# Controller.net
KiCad netlist of a schematic drawn in EasyEDA
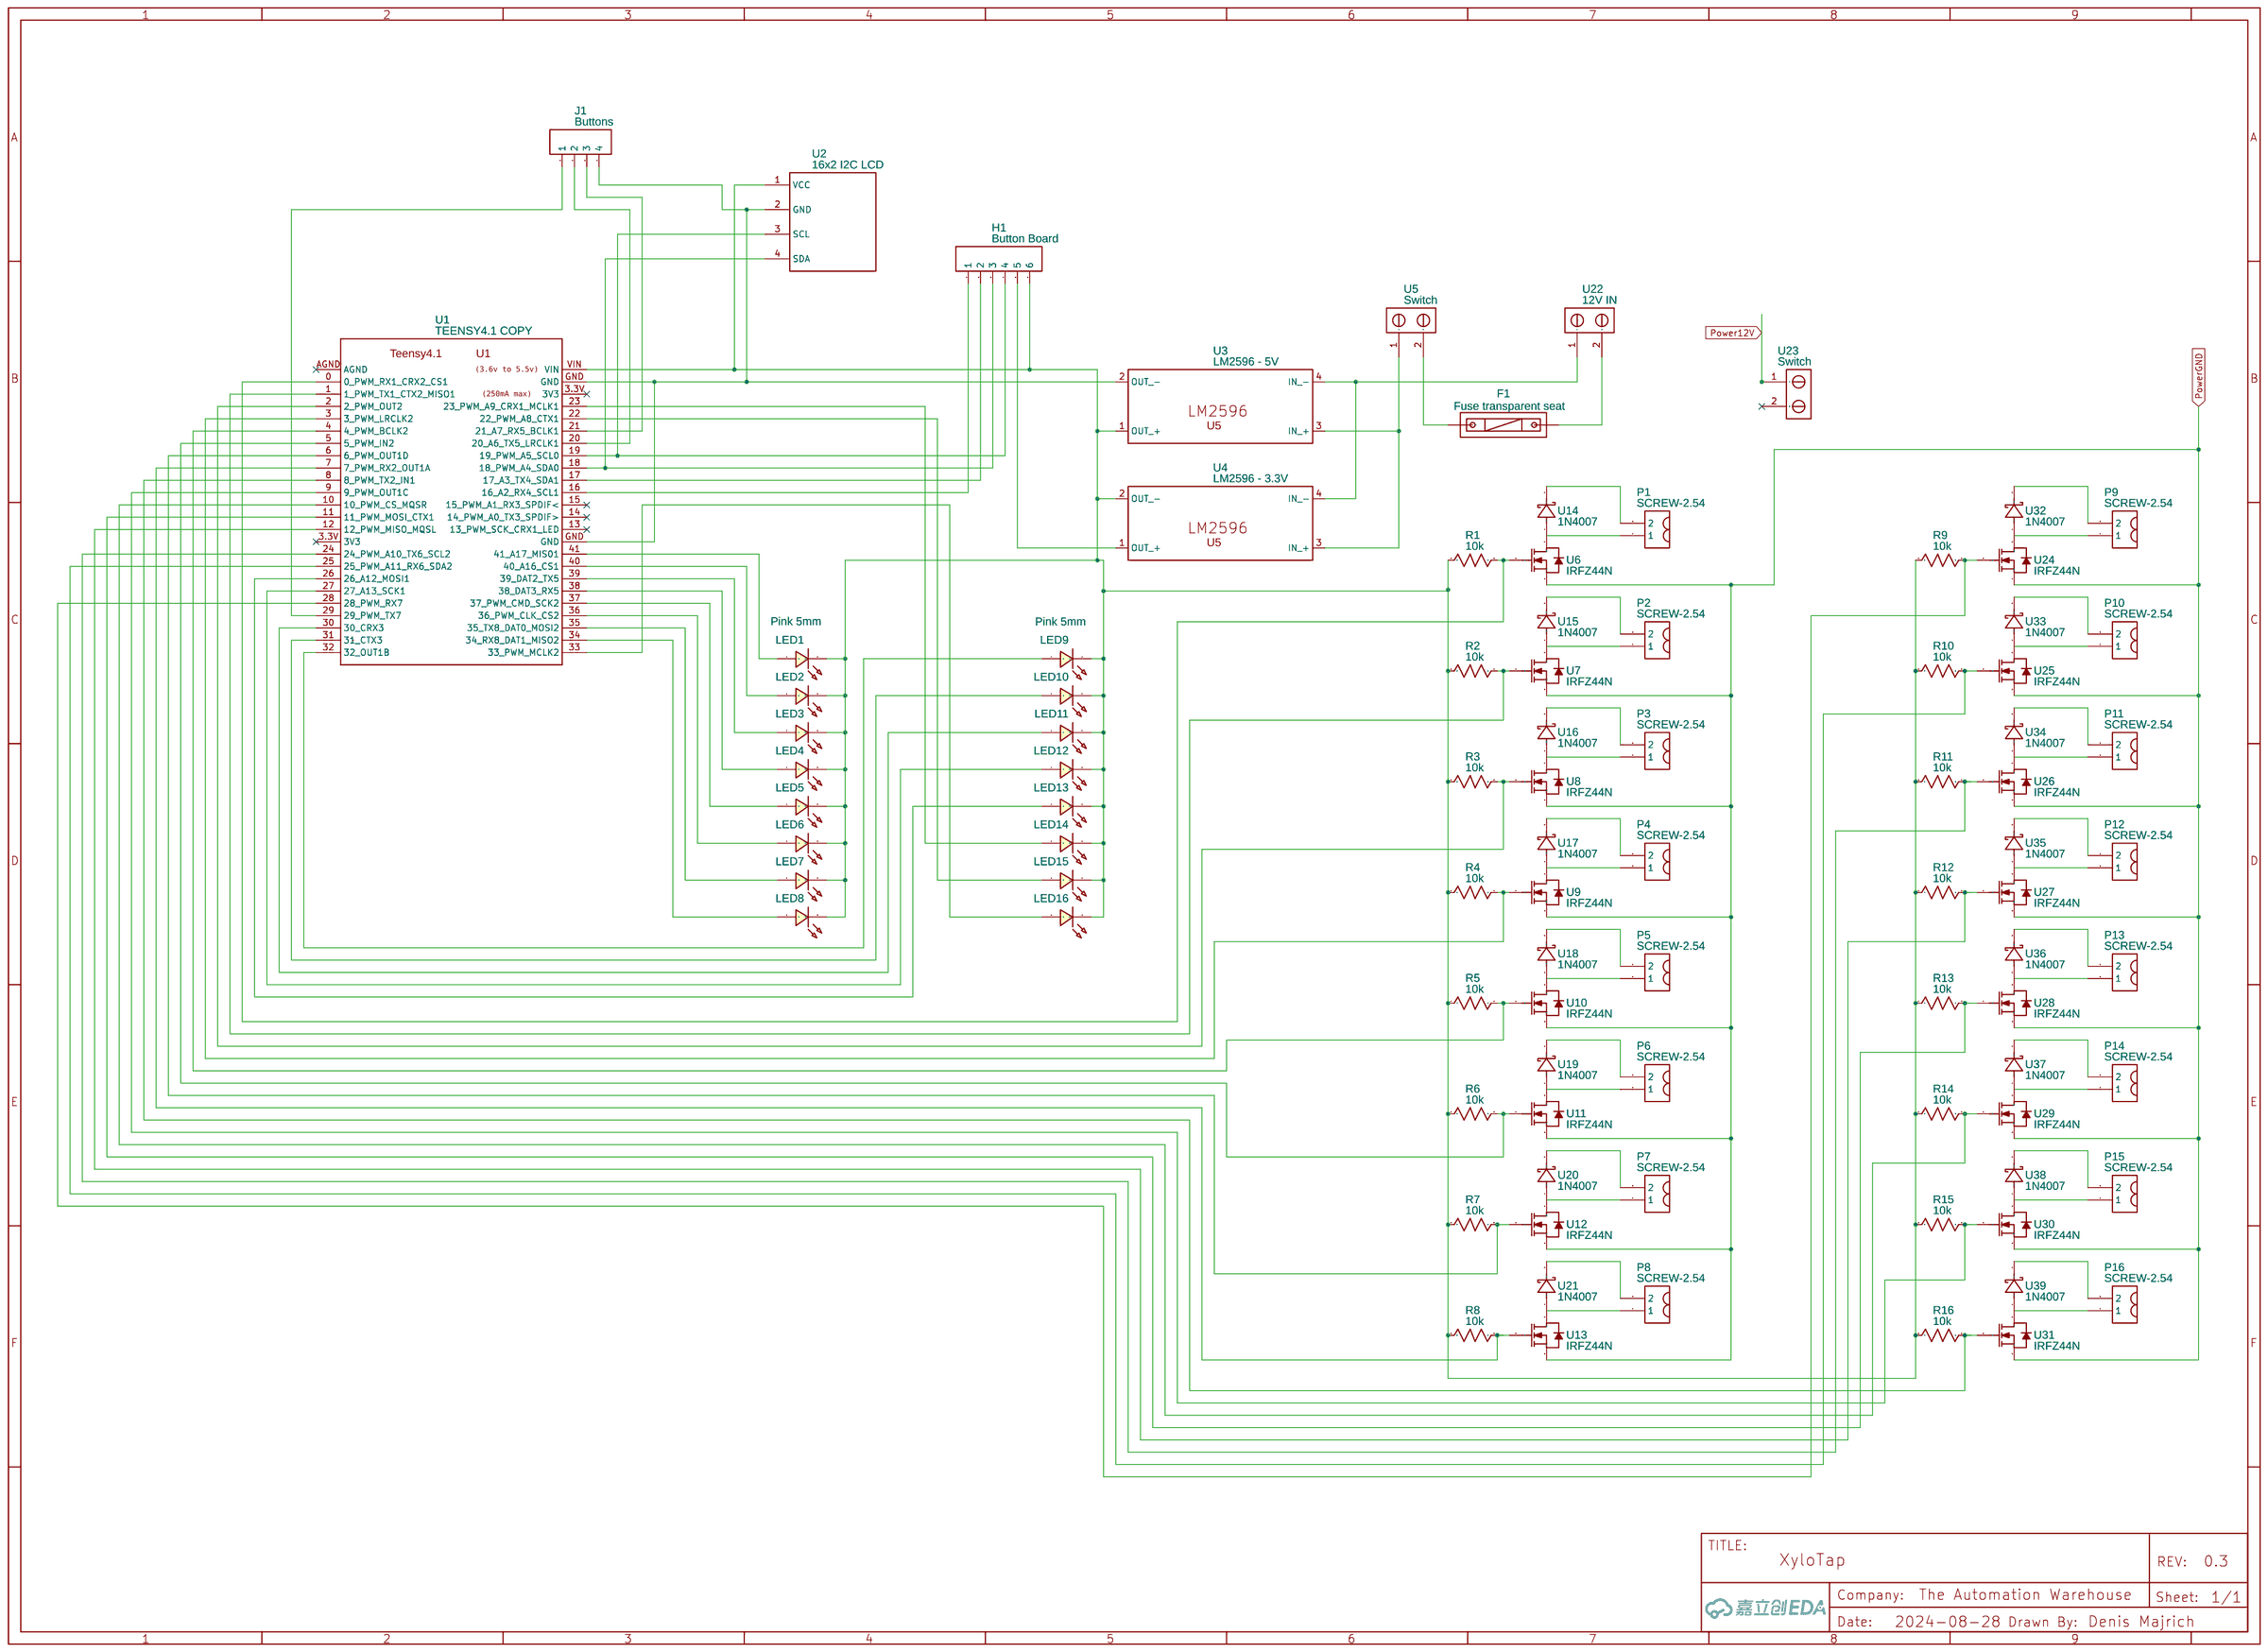
[diagram p0: schematic sheet]

(export (version "E")
  (design (tool "Eeschema 10.0.6"))
  (components
    (comp (ref "F1")
      (value "Fuse transparent seat")
      (fields (field (name "Manufacturer Part") "保险丝透明座") (field (name "Manufacturer") "xcfuse(旭程)"))
      (libsource (lib "") (part "Fuse transparent seat"))
    )
    (comp (ref "H1")
      (value "Button Board")
      (fields (field (name "BOM_Supplier Part") "C40877"))
      (libsource (lib "") (part "HDR-F-2.54_1x6"))
    )
    (comp (ref "J1")
      (value "Buttons")
      (fields (field (name "BOM_Supplier Part") "C124378"))
      (libsource (lib "") (part "HDR-M-2.54_1x4"))
    )
    (comp (ref "LED1") (value "Pink 5mm") (libsource (lib "") (part "LED-TH-5mm_B")))
    (comp (ref "LED2") (value "Pink 5mm") (libsource (lib "") (part "LED-TH-5mm_B")))
    (comp (ref "LED3") (value "Pink 5mm") (libsource (lib "") (part "LED-TH-5mm_B")))
    (comp (ref "LED4") (value "Pink 5mm") (libsource (lib "") (part "LED-TH-5mm_B")))
    (comp (ref "LED5") (value "Pink 5mm") (libsource (lib "") (part "LED-TH-5mm_B")))
    (comp (ref "LED6") (value "Pink 5mm") (libsource (lib "") (part "LED-TH-5mm_B")))
    (comp (ref "LED7") (value "Pink 5mm") (libsource (lib "") (part "LED-TH-5mm_B")))
    (comp (ref "LED8") (value "Pink 5mm") (libsource (lib "") (part "LED-TH-5mm_B")))
    (comp (ref "LED9") (value "Pink 5mm") (libsource (lib "") (part "LED-TH-5mm_B")))
    (comp (ref "LED10") (value "Pink 5mm") (libsource (lib "") (part "LED-TH-5mm_B")))
    (comp (ref "LED11") (value "Pink 5mm") (libsource (lib "") (part "LED-TH-5mm_B")))
    (comp (ref "LED12") (value "Pink 5mm") (libsource (lib "") (part "LED-TH-5mm_B")))
    (comp (ref "LED13") (value "Pink 5mm") (libsource (lib "") (part "LED-TH-5mm_B")))
    (comp (ref "LED14") (value "Pink 5mm") (libsource (lib "") (part "LED-TH-5mm_B")))
    (comp (ref "LED15") (value "Pink 5mm") (libsource (lib "") (part "LED-TH-5mm_B")))
    (comp (ref "LED16") (value "Pink 5mm") (libsource (lib "") (part "LED-TH-5mm_B")))
    (comp (ref "P1") (value "SCREW-2.54") (libsource (lib "") (part "PCBSCREW-2.54-2P")))
    (comp (ref "P2") (value "SCREW-2.54") (libsource (lib "") (part "PCBSCREW-2.54-2P")))
    (comp (ref "P3") (value "SCREW-2.54") (libsource (lib "") (part "PCBSCREW-2.54-2P")))
    (comp (ref "P4") (value "SCREW-2.54") (libsource (lib "") (part "PCBSCREW-2.54-2P")))
    (comp (ref "P5") (value "SCREW-2.54") (libsource (lib "") (part "PCBSCREW-2.54-2P")))
    (comp (ref "P6") (value "SCREW-2.54") (libsource (lib "") (part "PCBSCREW-2.54-2P")))
    (comp (ref "P7") (value "SCREW-2.54") (libsource (lib "") (part "PCBSCREW-2.54-2P")))
    (comp (ref "P8") (value "SCREW-2.54") (libsource (lib "") (part "PCBSCREW-2.54-2P")))
    (comp (ref "P9") (value "SCREW-2.54") (libsource (lib "") (part "PCBSCREW-2.54-2P")))
    (comp (ref "P10") (value "SCREW-2.54") (libsource (lib "") (part "PCBSCREW-2.54-2P")))
    (comp (ref "P11") (value "SCREW-2.54") (libsource (lib "") (part "PCBSCREW-2.54-2P")))
    (comp (ref "P12") (value "SCREW-2.54") (libsource (lib "") (part "PCBSCREW-2.54-2P")))
    (comp (ref "P13") (value "SCREW-2.54") (libsource (lib "") (part "PCBSCREW-2.54-2P")))
    (comp (ref "P14") (value "SCREW-2.54") (libsource (lib "") (part "PCBSCREW-2.54-2P")))
    (comp (ref "P15") (value "SCREW-2.54") (libsource (lib "") (part "PCBSCREW-2.54-2P")))
    (comp (ref "P16") (value "SCREW-2.54") (libsource (lib "") (part "PCBSCREW-2.54-2P")))
    (comp (ref "R1") (value "10k") (libsource (lib "") (part "R_AXIAL-0.4_US")))
    (comp (ref "R2") (value "10k") (libsource (lib "") (part "R_AXIAL-0.4_US")))
    (comp (ref "R3") (value "10k") (libsource (lib "") (part "R_AXIAL-0.4_US")))
    (comp (ref "R4") (value "10k") (libsource (lib "") (part "R_AXIAL-0.4_US")))
    (comp (ref "R5") (value "10k") (libsource (lib "") (part "R_AXIAL-0.4_US")))
    (comp (ref "R6") (value "10k") (libsource (lib "") (part "R_AXIAL-0.4_US")))
    (comp (ref "R7") (value "10k") (libsource (lib "") (part "R_AXIAL-0.4_US")))
    (comp (ref "R8") (value "10k") (libsource (lib "") (part "R_AXIAL-0.4_US")))
    (comp (ref "R9") (value "10k") (libsource (lib "") (part "R_AXIAL-0.4_US")))
    (comp (ref "R10") (value "10k") (libsource (lib "") (part "R_AXIAL-0.4_US")))
    (comp (ref "R11") (value "10k") (libsource (lib "") (part "R_AXIAL-0.4_US")))
    (comp (ref "R12") (value "10k") (libsource (lib "") (part "R_AXIAL-0.4_US")))
    (comp (ref "R13") (value "10k") (libsource (lib "") (part "R_AXIAL-0.4_US")))
    (comp (ref "R14") (value "10k") (libsource (lib "") (part "R_AXIAL-0.4_US")))
    (comp (ref "R15") (value "10k") (libsource (lib "") (part "R_AXIAL-0.4_US")))
    (comp (ref "R16") (value "10k") (libsource (lib "") (part "R_AXIAL-0.4_US")))
    (comp (ref "U1")
      (value "TEENSY4.1 COPY")
      (fields (field (name "BOM_Manufacturer Part") "Teensy4.1"))
      (libsource (lib "") (part "TEENSY4.1 COPY"))
    )
    (comp (ref "U2") (value "16x2 I2C LCD") (libsource (lib "") (part "16x2 i2c LCD no mount on PCB")))
    (comp (ref "U3")
      (value "LM2596 - 5V")
      (fields (field (name "BOM_Manufacturer Part") "LM2596ALEX"))
      (libsource (lib "") (part "LM2596ALEX"))
    )
    (comp (ref "U4")
      (value "LM2596 - 3.3V")
      (fields (field (name "BOM_Manufacturer Part") "LM2596ALEX"))
      (libsource (lib "") (part "LM2596ALEX"))
    )
    (comp (ref "U5") (value "Switch") (libsource (lib "") (part "Terminal_x2_5mm_1")))
    (comp (ref "U6")
      (value "IRFZ44N")
      (fields (field (name "Manufacturer") "minos(迈诺斯)"))
      (libsource (lib "") (part "IRFZ44N"))
    )
    (comp (ref "U7")
      (value "IRFZ44N")
      (fields (field (name "Manufacturer") "minos(迈诺斯)"))
      (libsource (lib "") (part "IRFZ44N"))
    )
    (comp (ref "U8")
      (value "IRFZ44N")
      (fields (field (name "Manufacturer") "minos(迈诺斯)"))
      (libsource (lib "") (part "IRFZ44N"))
    )
    (comp (ref "U9")
      (value "IRFZ44N")
      (fields (field (name "Manufacturer") "minos(迈诺斯)"))
      (libsource (lib "") (part "IRFZ44N"))
    )
    (comp (ref "U10")
      (value "IRFZ44N")
      (fields (field (name "Manufacturer") "minos(迈诺斯)"))
      (libsource (lib "") (part "IRFZ44N"))
    )
    (comp (ref "U11")
      (value "IRFZ44N")
      (fields (field (name "Manufacturer") "minos(迈诺斯)"))
      (libsource (lib "") (part "IRFZ44N"))
    )
    (comp (ref "U12")
      (value "IRFZ44N")
      (fields (field (name "Manufacturer") "minos(迈诺斯)"))
      (libsource (lib "") (part "IRFZ44N"))
    )
    (comp (ref "U13")
      (value "IRFZ44N")
      (fields (field (name "Manufacturer") "minos(迈诺斯)"))
      (libsource (lib "") (part "IRFZ44N"))
    )
    (comp (ref "U14")
      (value "1N4007")
      (fields (field (name "Manufacturer Part") "1N4007-DIODE"))
      (libsource (lib "") (part "1N4007-DIODE"))
    )
    (comp (ref "U15")
      (value "1N4007")
      (fields (field (name "Manufacturer Part") "1N4007-DIODE"))
      (libsource (lib "") (part "1N4007-DIODE"))
    )
    (comp (ref "U16")
      (value "1N4007")
      (fields (field (name "Manufacturer Part") "1N4007-DIODE"))
      (libsource (lib "") (part "1N4007-DIODE"))
    )
    (comp (ref "U17")
      (value "1N4007")
      (fields (field (name "Manufacturer Part") "1N4007-DIODE"))
      (libsource (lib "") (part "1N4007-DIODE"))
    )
    (comp (ref "U18")
      (value "1N4007")
      (fields (field (name "Manufacturer Part") "1N4007-DIODE"))
      (libsource (lib "") (part "1N4007-DIODE"))
    )
    (comp (ref "U19")
      (value "1N4007")
      (fields (field (name "Manufacturer Part") "1N4007-DIODE"))
      (libsource (lib "") (part "1N4007-DIODE"))
    )
    (comp (ref "U20")
      (value "1N4007")
      (fields (field (name "Manufacturer Part") "1N4007-DIODE"))
      (libsource (lib "") (part "1N4007-DIODE"))
    )
    (comp (ref "U21")
      (value "1N4007")
      (fields (field (name "Manufacturer Part") "1N4007-DIODE"))
      (libsource (lib "") (part "1N4007-DIODE"))
    )
    (comp (ref "U22") (value "12V IN") (libsource (lib "") (part "Terminal_x2_5mm_1")))
    (comp (ref "U23") (value "Switch") (libsource (lib "") (part "Terminal_x2_5mm")))
    (comp (ref "U24")
      (value "IRFZ44N")
      (fields (field (name "Manufacturer") "minos(迈诺斯)"))
      (libsource (lib "") (part "IRFZ44N"))
    )
    (comp (ref "U25")
      (value "IRFZ44N")
      (fields (field (name "Manufacturer") "minos(迈诺斯)"))
      (libsource (lib "") (part "IRFZ44N"))
    )
    (comp (ref "U26")
      (value "IRFZ44N")
      (fields (field (name "Manufacturer") "minos(迈诺斯)"))
      (libsource (lib "") (part "IRFZ44N"))
    )
    (comp (ref "U27")
      (value "IRFZ44N")
      (fields (field (name "Manufacturer") "minos(迈诺斯)"))
      (libsource (lib "") (part "IRFZ44N"))
    )
    (comp (ref "U28")
      (value "IRFZ44N")
      (fields (field (name "Manufacturer") "minos(迈诺斯)"))
      (libsource (lib "") (part "IRFZ44N"))
    )
    (comp (ref "U29")
      (value "IRFZ44N")
      (fields (field (name "Manufacturer") "minos(迈诺斯)"))
      (libsource (lib "") (part "IRFZ44N"))
    )
    (comp (ref "U30")
      (value "IRFZ44N")
      (fields (field (name "Manufacturer") "minos(迈诺斯)"))
      (libsource (lib "") (part "IRFZ44N"))
    )
    (comp (ref "U31")
      (value "IRFZ44N")
      (fields (field (name "Manufacturer") "minos(迈诺斯)"))
      (libsource (lib "") (part "IRFZ44N"))
    )
    (comp (ref "U32")
      (value "1N4007")
      (fields (field (name "Manufacturer Part") "1N4007-DIODE"))
      (libsource (lib "") (part "1N4007-DIODE"))
    )
    (comp (ref "U33")
      (value "1N4007")
      (fields (field (name "Manufacturer Part") "1N4007-DIODE"))
      (libsource (lib "") (part "1N4007-DIODE"))
    )
    (comp (ref "U34")
      (value "1N4007")
      (fields (field (name "Manufacturer Part") "1N4007-DIODE"))
      (libsource (lib "") (part "1N4007-DIODE"))
    )
    (comp (ref "U35")
      (value "1N4007")
      (fields (field (name "Manufacturer Part") "1N4007-DIODE"))
      (libsource (lib "") (part "1N4007-DIODE"))
    )
    (comp (ref "U36")
      (value "1N4007")
      (fields (field (name "Manufacturer Part") "1N4007-DIODE"))
      (libsource (lib "") (part "1N4007-DIODE"))
    )
    (comp (ref "U37")
      (value "1N4007")
      (fields (field (name "Manufacturer Part") "1N4007-DIODE"))
      (libsource (lib "") (part "1N4007-DIODE"))
    )
    (comp (ref "U38")
      (value "1N4007")
      (fields (field (name "Manufacturer Part") "1N4007-DIODE"))
      (libsource (lib "") (part "1N4007-DIODE"))
    )
    (comp (ref "U39")
      (value "1N4007")
      (fields (field (name "Manufacturer Part") "1N4007-DIODE"))
      (libsource (lib "") (part "1N4007-DIODE"))
    )
  )
  (nets
    (net (code "1") (name "Net-(F1-Pad1)") (class "Default")
      (node (ref "F1") (pin "1") (pinfunction "1_1") (pintype "unspecified"))
      (node (ref "U22") (pin "2") (pinfunction "2_2") (pintype "unspecified"))
    )
    (net (code "2") (name "Net-(F1-Pad2)") (class "Default")
      (node (ref "F1") (pin "2") (pinfunction "2_2") (pintype "unspecified"))
      (node (ref "U5") (pin "2") (pinfunction "2_2") (pintype "unspecified"))
    )
    (net (code "3") (name "Net-(U1-0_PWM_RX1_CRX2_CS1)") (class "Default")
      (node (ref "R1") (pin "2") (pinfunction "2_2") (pintype "unspecified"))
      (node (ref "U1") (pin "0") (pinfunction "0_PWM_RX1_CRX2_CS1_0") (pintype "bidirectional"))
      (node (ref "U6") (pin "1") (pinfunction "G_1") (pintype "unspecified"))
    )
    (net (code "4") (name "Net-(U1-1_PWM_TX1_CTX2_MISO1)") (class "Default")
      (node (ref "R2") (pin "2") (pinfunction "2_2") (pintype "unspecified"))
      (node (ref "U1") (pin "1") (pinfunction "1_PWM_TX1_CTX2_MISO1_1") (pintype "bidirectional"))
      (node (ref "U7") (pin "1") (pinfunction "G_1") (pintype "unspecified"))
    )
    (net (code "5") (name "Net-(U1-2_PWM_OUT2)") (class "Default")
      (node (ref "R3") (pin "2") (pinfunction "2_2") (pintype "unspecified"))
      (node (ref "U1") (pin "2") (pinfunction "2_PWM_OUT2_2") (pintype "bidirectional"))
      (node (ref "U8") (pin "1") (pinfunction "G_1") (pintype "unspecified"))
    )
    (net (code "6") (name "Net-(U1-3_PWM_LRCLK2)") (class "Default")
      (node (ref "R4") (pin "2") (pinfunction "2_2") (pintype "unspecified"))
      (node (ref "U1") (pin "3") (pinfunction "3_PWM_LRCLK2_3") (pintype "bidirectional"))
      (node (ref "U9") (pin "1") (pinfunction "G_1") (pintype "unspecified"))
    )
    (net (code "7") (name "Net-(U1-4_PWM_BCLK2)") (class "Default")
      (node (ref "R5") (pin "2") (pinfunction "2_2") (pintype "unspecified"))
      (node (ref "U1") (pin "4") (pinfunction "4_PWM_BCLK2_4") (pintype "bidirectional"))
      (node (ref "U10") (pin "1") (pinfunction "G_1") (pintype "unspecified"))
    )
    (net (code "8") (name "Net-(U1-5_PWM_IN2)") (class "Default")
      (node (ref "R6") (pin "2") (pinfunction "2_2") (pintype "unspecified"))
      (node (ref "U1") (pin "5") (pinfunction "5_PWM_IN2_5") (pintype "bidirectional"))
      (node (ref "U11") (pin "1") (pinfunction "G_1") (pintype "unspecified"))
    )
    (net (code "9") (name "Net-(U1-6_PWM_OUT1D)") (class "Default")
      (node (ref "R7") (pin "2") (pinfunction "2_2") (pintype "unspecified"))
      (node (ref "U1") (pin "6") (pinfunction "6_PWM_OUT1D_6") (pintype "bidirectional"))
      (node (ref "U12") (pin "1") (pinfunction "G_1") (pintype "unspecified"))
    )
    (net (code "10") (name "Net-(U1-7_PWM_RX2_OUT1A)") (class "Default")
      (node (ref "R8") (pin "2") (pinfunction "2_2") (pintype "unspecified"))
      (node (ref "U1") (pin "7") (pinfunction "7_PWM_RX2_OUT1A_7") (pintype "bidirectional"))
      (node (ref "U13") (pin "1") (pinfunction "G_1") (pintype "unspecified"))
    )
    (net (code "11") (name "Net-(U1-8_PWM_TX2_IN1)") (class "Default")
      (node (ref "R16") (pin "2") (pinfunction "2_2") (pintype "unspecified"))
      (node (ref "U1") (pin "8") (pinfunction "8_PWM_TX2_IN1_8") (pintype "bidirectional"))
      (node (ref "U31") (pin "1") (pinfunction "G_1") (pintype "unspecified"))
    )
    (net (code "12") (name "Net-(U1-9_PWM_OUT1C)") (class "Default")
      (node (ref "R15") (pin "2") (pinfunction "2_2") (pintype "unspecified"))
      (node (ref "U1") (pin "9") (pinfunction "9_PWM_OUT1C_9") (pintype "bidirectional"))
      (node (ref "U30") (pin "1") (pinfunction "G_1") (pintype "unspecified"))
    )
    (net (code "13") (name "Net-(U1-10_PWM_CS_MQSR)") (class "Default")
      (node (ref "R14") (pin "2") (pinfunction "2_2") (pintype "unspecified"))
      (node (ref "U1") (pin "10") (pinfunction "10_PWM_CS_MQSR_10") (pintype "bidirectional"))
      (node (ref "U29") (pin "1") (pinfunction "G_1") (pintype "unspecified"))
    )
    (net (code "14") (name "Net-(U1-11_PWM_MOSI_CTX1)") (class "Default")
      (node (ref "R13") (pin "2") (pinfunction "2_2") (pintype "unspecified"))
      (node (ref "U1") (pin "11") (pinfunction "11_PWM_MOSI_CTX1_11") (pintype "bidirectional"))
      (node (ref "U28") (pin "1") (pinfunction "G_1") (pintype "unspecified"))
    )
    (net (code "15") (name "Net-(U1-12_PWM_MISO_MQSL)") (class "Default")
      (node (ref "R12") (pin "2") (pinfunction "2_2") (pintype "unspecified"))
      (node (ref "U1") (pin "12") (pinfunction "12_PWM_MISO_MQSL_12") (pintype "bidirectional"))
      (node (ref "U27") (pin "1") (pinfunction "G_1") (pintype "unspecified"))
    )
    (net (code "16") (name "Net-(U1-16_A2_RX4_SCL1)") (class "Default")
      (node (ref "H1") (pin "1") (pinfunction "1_1") (pintype "input"))
      (node (ref "U1") (pin "16") (pinfunction "16_A2_RX4_SCL1_16") (pintype "bidirectional"))
    )
    (net (code "17") (name "Net-(U1-17_A3_TX4_SDA1)") (class "Default")
      (node (ref "H1") (pin "2") (pinfunction "2_2") (pintype "input"))
      (node (ref "U1") (pin "17") (pinfunction "17_A3_TX4_SDA1_17") (pintype "bidirectional"))
    )
    (net (code "18") (name "Net-(U1-18_PWM_A4_SDA0)") (class "Default")
      (node (ref "H1") (pin "3") (pinfunction "3_3") (pintype "input"))
      (node (ref "U1") (pin "18") (pinfunction "18_PWM_A4_SDA0_18") (pintype "bidirectional"))
      (node (ref "U2") (pin "4") (pinfunction "SDA_4") (pintype "unspecified"))
    )
    (net (code "19") (name "Net-(U1-19_PWM_A5_SCL0)") (class "Default")
      (node (ref "H1") (pin "4") (pinfunction "4_4") (pintype "input"))
      (node (ref "U1") (pin "19") (pinfunction "19_PWM_A5_SCL0_19") (pintype "bidirectional"))
      (node (ref "U2") (pin "3") (pinfunction "SCL_3") (pintype "unspecified"))
    )
    (net (code "20") (name "Net-(U1-20_A6_TX5_LRCLK1)") (class "Default")
      (node (ref "J1") (pin "2") (pinfunction "2_2") (pintype "unspecified"))
      (node (ref "U1") (pin "20") (pinfunction "20_A6_TX5_LRCLK1_20") (pintype "bidirectional"))
    )
    (net (code "21") (name "Net-(U1-21_A7_RX5_BCLK1)") (class "Default")
      (node (ref "J1") (pin "3") (pinfunction "3_3") (pintype "unspecified"))
      (node (ref "U1") (pin "21") (pinfunction "21_A7_RX5_BCLK1_21") (pintype "bidirectional"))
    )
    (net (code "22") (name "Net-(U1-22_PWM_A8_CTX1)") (class "Default")
      (node (ref "LED15") (pin "1") (pinfunction "1_1") (pintype "unspecified"))
      (node (ref "U1") (pin "22") (pinfunction "22_PWM_A8_CTX1_22") (pintype "bidirectional"))
    )
    (net (code "23") (name "Net-(U1-23_PWM_A9_CRX1_MCLK1)") (class "Default")
      (node (ref "LED14") (pin "1") (pinfunction "1_1") (pintype "unspecified"))
      (node (ref "U1") (pin "23") (pinfunction "23_PWM_A9_CRX1_MCLK1_23") (pintype "bidirectional"))
    )
    (net (code "24") (name "Net-(U1-24_PWM_A10_TX6_SCL2)") (class "Default")
      (node (ref "R11") (pin "2") (pinfunction "2_2") (pintype "unspecified"))
      (node (ref "U1") (pin "24") (pinfunction "24_PWM_A10_TX6_SCL2_24") (pintype "bidirectional"))
      (node (ref "U26") (pin "1") (pinfunction "G_1") (pintype "unspecified"))
    )
    (net (code "25") (name "Net-(U1-25_PWM_A11_RX6_SDA2)") (class "Default")
      (node (ref "R10") (pin "2") (pinfunction "2_2") (pintype "unspecified"))
      (node (ref "U1") (pin "25") (pinfunction "25_PWM_A11_RX6_SDA2_25") (pintype "bidirectional"))
      (node (ref "U25") (pin "1") (pinfunction "G_1") (pintype "unspecified"))
    )
    (net (code "26") (name "Net-(U1-26_A12_MOSI1)") (class "Default")
      (node (ref "LED13") (pin "1") (pinfunction "1_1") (pintype "unspecified"))
      (node (ref "U1") (pin "26") (pinfunction "26_A12_MOSI1_26") (pintype "bidirectional"))
    )
    (net (code "27") (name "Net-(U1-27_A13_SCK1)") (class "Default")
      (node (ref "LED12") (pin "1") (pinfunction "1_1") (pintype "unspecified"))
      (node (ref "U1") (pin "27") (pinfunction "27_A13_SCK1_27") (pintype "bidirectional"))
    )
    (net (code "28") (name "Net-(U1-28_PWM_RX7)") (class "Default")
      (node (ref "R9") (pin "2") (pinfunction "2_2") (pintype "unspecified"))
      (node (ref "U1") (pin "28") (pinfunction "28_PWM_RX7_28") (pintype "bidirectional"))
      (node (ref "U24") (pin "1") (pinfunction "G_1") (pintype "unspecified"))
    )
    (net (code "29") (name "Net-(U1-29_PWM_TX7)") (class "Default")
      (node (ref "J1") (pin "1") (pinfunction "1_1") (pintype "unspecified"))
      (node (ref "U1") (pin "29") (pinfunction "29_PWM_TX7_29") (pintype "bidirectional"))
    )
    (net (code "30") (name "Net-(U1-30_CRX3)") (class "Default")
      (node (ref "LED11") (pin "1") (pinfunction "1_1") (pintype "unspecified"))
      (node (ref "U1") (pin "30") (pinfunction "30_CRX3_30") (pintype "bidirectional"))
    )
    (net (code "31") (name "Net-(U1-31_CTX3)") (class "Default")
      (node (ref "LED10") (pin "1") (pinfunction "1_1") (pintype "unspecified"))
      (node (ref "U1") (pin "31") (pinfunction "31_CTX3_31") (pintype "bidirectional"))
    )
    (net (code "32") (name "Net-(U1-32_OUT1B)") (class "Default")
      (node (ref "LED9") (pin "1") (pinfunction "1_1") (pintype "unspecified"))
      (node (ref "U1") (pin "32") (pinfunction "32_OUT1B_32") (pintype "bidirectional"))
    )
    (net (code "33") (name "Net-(U1-33_PWM_MCLK2)") (class "Default")
      (node (ref "LED16") (pin "1") (pinfunction "1_1") (pintype "unspecified"))
      (node (ref "U1") (pin "33") (pinfunction "33_PWM_MCLK2_33") (pintype "bidirectional"))
    )
    (net (code "34") (name "Net-(U1-34_RX8_DAT1_MISO2)") (class "Default")
      (node (ref "LED8") (pin "1") (pinfunction "1_1") (pintype "unspecified"))
      (node (ref "U1") (pin "34") (pinfunction "34_RX8_DAT1_MISO2_34") (pintype "bidirectional"))
    )
    (net (code "35") (name "Net-(U1-35_TX8_DAT0_MOSI2)") (class "Default")
      (node (ref "LED7") (pin "1") (pinfunction "1_1") (pintype "unspecified"))
      (node (ref "U1") (pin "35") (pinfunction "35_TX8_DAT0_MOSI2_35") (pintype "bidirectional"))
    )
    (net (code "36") (name "Net-(U1-36_PWM_CLK_CS2)") (class "Default")
      (node (ref "LED6") (pin "1") (pinfunction "1_1") (pintype "unspecified"))
      (node (ref "U1") (pin "36") (pinfunction "36_PWM_CLK_CS2_36") (pintype "bidirectional"))
    )
    (net (code "37") (name "Net-(U1-37_PWM_CMD_SCK2)") (class "Default")
      (node (ref "LED5") (pin "1") (pinfunction "1_1") (pintype "unspecified"))
      (node (ref "U1") (pin "37") (pinfunction "37_PWM_CMD_SCK2_37") (pintype "bidirectional"))
    )
    (net (code "38") (name "Net-(U1-38_DAT3_RX5)") (class "Default")
      (node (ref "LED4") (pin "1") (pinfunction "1_1") (pintype "unspecified"))
      (node (ref "U1") (pin "38") (pinfunction "38_DAT3_RX5_38") (pintype "bidirectional"))
    )
    (net (code "39") (name "Net-(U1-39_DAT2_TX5)") (class "Default")
      (node (ref "LED3") (pin "1") (pinfunction "1_1") (pintype "unspecified"))
      (node (ref "U1") (pin "39") (pinfunction "39_DAT2_TX5_39") (pintype "bidirectional"))
    )
    (net (code "40") (name "Net-(U1-40_A16_CS1)") (class "Default")
      (node (ref "LED2") (pin "1") (pinfunction "1_1") (pintype "unspecified"))
      (node (ref "U1") (pin "40") (pinfunction "40_A16_CS1_40") (pintype "bidirectional"))
    )
    (net (code "41") (name "Net-(U1-41_A17_MIS01)") (class "Default")
      (node (ref "LED1") (pin "1") (pinfunction "1_1") (pintype "unspecified"))
      (node (ref "U1") (pin "41") (pinfunction "41_A17_MIS01_41") (pintype "bidirectional"))
    )
    (net (code "42") (name "Net-(U2-GND)") (class "Default")
      (node (ref "J1") (pin "4") (pinfunction "4_4") (pintype "unspecified"))
      (node (ref "U1") (pin "GND") (pinfunction "GND_GND") (pintype "bidirectional"))
      (node (ref "U2") (pin "2") (pinfunction "GND_2") (pintype "unspecified"))
      (node (ref "U3") (pin "2") (pinfunction "OUT_-_2") (pintype "unspecified"))
    )
    (net (code "43") (name "Net-(U2-VCC)") (class "Default")
      (node (ref "H1") (pin "6") (pinfunction "6_6") (pintype "input"))
      (node (ref "LED1") (pin "2") (pinfunction "2_2") (pintype "unspecified"))
      (node (ref "LED10") (pin "2") (pinfunction "2_2") (pintype "unspecified"))
      (node (ref "LED11") (pin "2") (pinfunction "2_2") (pintype "unspecified"))
      (node (ref "LED12") (pin "2") (pinfunction "2_2") (pintype "unspecified"))
      (node (ref "LED13") (pin "2") (pinfunction "2_2") (pintype "unspecified"))
      (node (ref "LED14") (pin "2") (pinfunction "2_2") (pintype "unspecified"))
      (node (ref "LED15") (pin "2") (pinfunction "2_2") (pintype "unspecified"))
      (node (ref "LED16") (pin "2") (pinfunction "2_2") (pintype "unspecified"))
      (node (ref "LED2") (pin "2") (pinfunction "2_2") (pintype "unspecified"))
      (node (ref "LED3") (pin "2") (pinfunction "2_2") (pintype "unspecified"))
      (node (ref "LED4") (pin "2") (pinfunction "2_2") (pintype "unspecified"))
      (node (ref "LED5") (pin "2") (pinfunction "2_2") (pintype "unspecified"))
      (node (ref "LED6") (pin "2") (pinfunction "2_2") (pintype "unspecified"))
      (node (ref "LED7") (pin "2") (pinfunction "2_2") (pintype "unspecified"))
      (node (ref "LED8") (pin "2") (pinfunction "2_2") (pintype "unspecified"))
      (node (ref "LED9") (pin "2") (pinfunction "2_2") (pintype "unspecified"))
      (node (ref "R1") (pin "1") (pinfunction "1_1") (pintype "unspecified"))
      (node (ref "R10") (pin "1") (pinfunction "1_1") (pintype "unspecified"))
      (node (ref "R11") (pin "1") (pinfunction "1_1") (pintype "unspecified"))
      (node (ref "R12") (pin "1") (pinfunction "1_1") (pintype "unspecified"))
      (node (ref "R13") (pin "1") (pinfunction "1_1") (pintype "unspecified"))
      (node (ref "R14") (pin "1") (pinfunction "1_1") (pintype "unspecified"))
      (node (ref "R15") (pin "1") (pinfunction "1_1") (pintype "unspecified"))
      (node (ref "R16") (pin "1") (pinfunction "1_1") (pintype "unspecified"))
      (node (ref "R2") (pin "1") (pinfunction "1_1") (pintype "unspecified"))
      (node (ref "R3") (pin "1") (pinfunction "1_1") (pintype "unspecified"))
      (node (ref "R4") (pin "1") (pinfunction "1_1") (pintype "unspecified"))
      (node (ref "R5") (pin "1") (pinfunction "1_1") (pintype "unspecified"))
      (node (ref "R6") (pin "1") (pinfunction "1_1") (pintype "unspecified"))
      (node (ref "R7") (pin "1") (pinfunction "1_1") (pintype "unspecified"))
      (node (ref "R8") (pin "1") (pinfunction "1_1") (pintype "unspecified"))
      (node (ref "R9") (pin "1") (pinfunction "1_1") (pintype "unspecified"))
      (node (ref "U1") (pin "VIN") (pinfunction "VIN_VIN") (pintype "bidirectional"))
      (node (ref "U2") (pin "1") (pinfunction "VCC_1") (pintype "unspecified"))
      (node (ref "U3") (pin "1") (pinfunction "OUT_+_1") (pintype "unspecified"))
      (node (ref "U4") (pin "2") (pinfunction "OUT_-_2") (pintype "unspecified"))
    )
    (net (code "44") (name "Net-(U3-IN_+)") (class "Default")
      (node (ref "U3") (pin "3") (pinfunction "IN_+_3") (pintype "unspecified"))
      (node (ref "U4") (pin "3") (pinfunction "IN_+_3") (pintype "unspecified"))
      (node (ref "U5") (pin "1") (pinfunction "1_1") (pintype "unspecified"))
    )
    (net (code "45") (name "Net-(U3-IN_-)") (class "Default")
      (node (ref "U22") (pin "1") (pinfunction "1_1") (pintype "unspecified"))
      (node (ref "U3") (pin "4") (pinfunction "IN_-_4") (pintype "unspecified"))
      (node (ref "U4") (pin "4") (pinfunction "IN_-_4") (pintype "unspecified"))
    )
    (net (code "46") (name "Net-(U4-OUT_+)") (class "Default")
      (node (ref "H1") (pin "5") (pinfunction "5_5") (pintype "input"))
      (node (ref "U4") (pin "1") (pinfunction "OUT_+_1") (pintype "unspecified"))
    )
    (net (code "47") (name "Net-(U10-D)") (class "Default")
      (node (ref "P5") (pin "1") (pinfunction "1_1") (pintype "unspecified"))
      (node (ref "U10") (pin "2") (pinfunction "D_2") (pintype "unspecified"))
      (node (ref "U18") (pin "1") (pinfunction "A_1") (pintype "unspecified"))
    )
    (net (code "48") (name "Net-(U11-D)") (class "Default")
      (node (ref "P6") (pin "1") (pinfunction "1_1") (pintype "unspecified"))
      (node (ref "U11") (pin "2") (pinfunction "D_2") (pintype "unspecified"))
      (node (ref "U19") (pin "1") (pinfunction "A_1") (pintype "unspecified"))
    )
    (net (code "49") (name "Net-(U12-D)") (class "Default")
      (node (ref "P7") (pin "1") (pinfunction "1_1") (pintype "unspecified"))
      (node (ref "U12") (pin "2") (pinfunction "D_2") (pintype "unspecified"))
      (node (ref "U20") (pin "1") (pinfunction "A_1") (pintype "unspecified"))
    )
    (net (code "50") (name "Net-(U13-D)") (class "Default")
      (node (ref "P8") (pin "1") (pinfunction "1_1") (pintype "unspecified"))
      (node (ref "U13") (pin "2") (pinfunction "D_2") (pintype "unspecified"))
      (node (ref "U21") (pin "1") (pinfunction "A_1") (pintype "unspecified"))
    )
    (net (code "51") (name "Net-(U14-A)") (class "Default")
      (node (ref "P1") (pin "1") (pinfunction "1_1") (pintype "unspecified"))
      (node (ref "U14") (pin "1") (pinfunction "A_1") (pintype "unspecified"))
      (node (ref "U6") (pin "2") (pinfunction "D_2") (pintype "unspecified"))
    )
    (net (code "52") (name "Net-(U14-K)") (class "Default")
      (node (ref "P1") (pin "2") (pinfunction "2_2") (pintype "unspecified"))
      (node (ref "U14") (pin "2") (pinfunction "K_2") (pintype "unspecified"))
    )
    (net (code "53") (name "Net-(U15-A)") (class "Default")
      (node (ref "P2") (pin "1") (pinfunction "1_1") (pintype "unspecified"))
      (node (ref "U15") (pin "1") (pinfunction "A_1") (pintype "unspecified"))
      (node (ref "U7") (pin "2") (pinfunction "D_2") (pintype "unspecified"))
    )
    (net (code "54") (name "Net-(U15-K)") (class "Default")
      (node (ref "P2") (pin "2") (pinfunction "2_2") (pintype "unspecified"))
      (node (ref "U15") (pin "2") (pinfunction "K_2") (pintype "unspecified"))
    )
    (net (code "55") (name "Net-(U16-A)") (class "Default")
      (node (ref "P3") (pin "1") (pinfunction "1_1") (pintype "unspecified"))
      (node (ref "U16") (pin "1") (pinfunction "A_1") (pintype "unspecified"))
      (node (ref "U8") (pin "2") (pinfunction "D_2") (pintype "unspecified"))
    )
    (net (code "56") (name "Net-(U16-K)") (class "Default")
      (node (ref "P3") (pin "2") (pinfunction "2_2") (pintype "unspecified"))
      (node (ref "U16") (pin "2") (pinfunction "K_2") (pintype "unspecified"))
    )
    (net (code "57") (name "Net-(U17-A)") (class "Default")
      (node (ref "P4") (pin "1") (pinfunction "1_1") (pintype "unspecified"))
      (node (ref "U17") (pin "1") (pinfunction "A_1") (pintype "unspecified"))
      (node (ref "U9") (pin "2") (pinfunction "D_2") (pintype "unspecified"))
    )
    (net (code "58") (name "Net-(U17-K)") (class "Default")
      (node (ref "P4") (pin "2") (pinfunction "2_2") (pintype "unspecified"))
      (node (ref "U17") (pin "2") (pinfunction "K_2") (pintype "unspecified"))
    )
    (net (code "59") (name "Net-(U18-K)") (class "Default")
      (node (ref "P5") (pin "2") (pinfunction "2_2") (pintype "unspecified"))
      (node (ref "U18") (pin "2") (pinfunction "K_2") (pintype "unspecified"))
    )
    (net (code "60") (name "Net-(U19-K)") (class "Default")
      (node (ref "P6") (pin "2") (pinfunction "2_2") (pintype "unspecified"))
      (node (ref "U19") (pin "2") (pinfunction "K_2") (pintype "unspecified"))
    )
    (net (code "61") (name "Net-(U20-K)") (class "Default")
      (node (ref "P7") (pin "2") (pinfunction "2_2") (pintype "unspecified"))
      (node (ref "U20") (pin "2") (pinfunction "K_2") (pintype "unspecified"))
    )
    (net (code "62") (name "Net-(U21-K)") (class "Default")
      (node (ref "P8") (pin "2") (pinfunction "2_2") (pintype "unspecified"))
      (node (ref "U21") (pin "2") (pinfunction "K_2") (pintype "unspecified"))
    )
    (net (code "63") (name "Net-(U24-D)") (class "Default")
      (node (ref "P9") (pin "1") (pinfunction "1_1") (pintype "unspecified"))
      (node (ref "U24") (pin "2") (pinfunction "D_2") (pintype "unspecified"))
      (node (ref "U32") (pin "1") (pinfunction "A_1") (pintype "unspecified"))
    )
    (net (code "64") (name "Net-(U25-D)") (class "Default")
      (node (ref "P10") (pin "1") (pinfunction "1_1") (pintype "unspecified"))
      (node (ref "U25") (pin "2") (pinfunction "D_2") (pintype "unspecified"))
      (node (ref "U33") (pin "1") (pinfunction "A_1") (pintype "unspecified"))
    )
    (net (code "65") (name "Net-(U26-D)") (class "Default")
      (node (ref "P11") (pin "1") (pinfunction "1_1") (pintype "unspecified"))
      (node (ref "U26") (pin "2") (pinfunction "D_2") (pintype "unspecified"))
      (node (ref "U34") (pin "1") (pinfunction "A_1") (pintype "unspecified"))
    )
    (net (code "66") (name "Net-(U27-D)") (class "Default")
      (node (ref "P12") (pin "1") (pinfunction "1_1") (pintype "unspecified"))
      (node (ref "U27") (pin "2") (pinfunction "D_2") (pintype "unspecified"))
      (node (ref "U35") (pin "1") (pinfunction "A_1") (pintype "unspecified"))
    )
    (net (code "67") (name "Net-(U28-D)") (class "Default")
      (node (ref "P13") (pin "1") (pinfunction "1_1") (pintype "unspecified"))
      (node (ref "U28") (pin "2") (pinfunction "D_2") (pintype "unspecified"))
      (node (ref "U36") (pin "1") (pinfunction "A_1") (pintype "unspecified"))
    )
    (net (code "68") (name "Net-(U29-D)") (class "Default")
      (node (ref "P14") (pin "1") (pinfunction "1_1") (pintype "unspecified"))
      (node (ref "U29") (pin "2") (pinfunction "D_2") (pintype "unspecified"))
      (node (ref "U37") (pin "1") (pinfunction "A_1") (pintype "unspecified"))
    )
    (net (code "69") (name "Net-(U30-D)") (class "Default")
      (node (ref "P15") (pin "1") (pinfunction "1_1") (pintype "unspecified"))
      (node (ref "U30") (pin "2") (pinfunction "D_2") (pintype "unspecified"))
      (node (ref "U38") (pin "1") (pinfunction "A_1") (pintype "unspecified"))
    )
    (net (code "70") (name "Net-(U31-D)") (class "Default")
      (node (ref "P16") (pin "1") (pinfunction "1_1") (pintype "unspecified"))
      (node (ref "U31") (pin "2") (pinfunction "D_2") (pintype "unspecified"))
      (node (ref "U39") (pin "1") (pinfunction "A_1") (pintype "unspecified"))
    )
    (net (code "71") (name "Net-(U32-K)") (class "Default")
      (node (ref "P9") (pin "2") (pinfunction "2_2") (pintype "unspecified"))
      (node (ref "U32") (pin "2") (pinfunction "K_2") (pintype "unspecified"))
    )
    (net (code "72") (name "Net-(U33-K)") (class "Default")
      (node (ref "P10") (pin "2") (pinfunction "2_2") (pintype "unspecified"))
      (node (ref "U33") (pin "2") (pinfunction "K_2") (pintype "unspecified"))
    )
    (net (code "73") (name "Net-(U34-K)") (class "Default")
      (node (ref "P11") (pin "2") (pinfunction "2_2") (pintype "unspecified"))
      (node (ref "U34") (pin "2") (pinfunction "K_2") (pintype "unspecified"))
    )
    (net (code "74") (name "Net-(U35-K)") (class "Default")
      (node (ref "P12") (pin "2") (pinfunction "2_2") (pintype "unspecified"))
      (node (ref "U35") (pin "2") (pinfunction "K_2") (pintype "unspecified"))
    )
    (net (code "75") (name "Net-(U36-K)") (class "Default")
      (node (ref "P13") (pin "2") (pinfunction "2_2") (pintype "unspecified"))
      (node (ref "U36") (pin "2") (pinfunction "K_2") (pintype "unspecified"))
    )
    (net (code "76") (name "Net-(U37-K)") (class "Default")
      (node (ref "P14") (pin "2") (pinfunction "2_2") (pintype "unspecified"))
      (node (ref "U37") (pin "2") (pinfunction "K_2") (pintype "unspecified"))
    )
    (net (code "77") (name "Net-(U38-K)") (class "Default")
      (node (ref "P15") (pin "2") (pinfunction "2_2") (pintype "unspecified"))
      (node (ref "U38") (pin "2") (pinfunction "K_2") (pintype "unspecified"))
    )
    (net (code "78") (name "Net-(U39-K)") (class "Default")
      (node (ref "P16") (pin "2") (pinfunction "2_2") (pintype "unspecified"))
      (node (ref "U39") (pin "2") (pinfunction "K_2") (pintype "unspecified"))
    )
    (net (code "79") (name "Power12V") (class "Default")
      (node (ref "U23") (pin "1") (pinfunction "1_1") (pintype "unspecified"))
    )
    (net (code "80") (name "PowerGND") (class "Default")
      (node (ref "U10") (pin "3") (pinfunction "S_3") (pintype "unspecified"))
      (node (ref "U11") (pin "3") (pinfunction "S_3") (pintype "unspecified"))
      (node (ref "U12") (pin "3") (pinfunction "S_3") (pintype "unspecified"))
      (node (ref "U13") (pin "3") (pinfunction "S_3") (pintype "unspecified"))
      (node (ref "U24") (pin "3") (pinfunction "S_3") (pintype "unspecified"))
      (node (ref "U25") (pin "3") (pinfunction "S_3") (pintype "unspecified"))
      (node (ref "U26") (pin "3") (pinfunction "S_3") (pintype "unspecified"))
      (node (ref "U27") (pin "3") (pinfunction "S_3") (pintype "unspecified"))
      (node (ref "U28") (pin "3") (pinfunction "S_3") (pintype "unspecified"))
      (node (ref "U29") (pin "3") (pinfunction "S_3") (pintype "unspecified"))
      (node (ref "U30") (pin "3") (pinfunction "S_3") (pintype "unspecified"))
      (node (ref "U31") (pin "3") (pinfunction "S_3") (pintype "unspecified"))
      (node (ref "U6") (pin "3") (pinfunction "S_3") (pintype "unspecified"))
      (node (ref "U7") (pin "3") (pinfunction "S_3") (pintype "unspecified"))
      (node (ref "U8") (pin "3") (pinfunction "S_3") (pintype "unspecified"))
      (node (ref "U9") (pin "3") (pinfunction "S_3") (pintype "unspecified"))
    )
    (net (code "81") (name "unconnected-(U1-3V3-Pad3.3V)") (class "Default")
      (node (ref "U1") (pin "3.3V") (pinfunction "3V3_3.3V") (pintype "bidirectional+no_connect"))
    )
    (net (code "82") (name "unconnected-(U1-3V3-Pad3.3V)_1") (class "Default")
      (node (ref "U1") (pin "3.3V") (pinfunction "3V3_3.3V") (pintype "bidirectional+no_connect"))
    )
    (net (code "83") (name "unconnected-(U1-13_PWM_SCK_CRX1_LED-Pad13)") (class "Default")
      (node (ref "U1") (pin "13") (pinfunction "13_PWM_SCK_CRX1_LED_13") (pintype "bidirectional"))
    )
    (net (code "84") (name "unconnected-(U1-14_PWM_A0_TX3_SPDIF>-Pad14)") (class "Default")
      (node (ref "U1") (pin "14") (pinfunction "14_PWM_A0_TX3_SPDIF>_14") (pintype "bidirectional"))
    )
    (net (code "85") (name "unconnected-(U1-15_PWM_A1_RX3_SPDIF<-Pad15)") (class "Default")
      (node (ref "U1") (pin "15") (pinfunction "15_PWM_A1_RX3_SPDIF<_15") (pintype "bidirectional"))
    )
    (net (code "86") (name "unconnected-(U1-PadAGND)") (class "Default")
      (node (ref "U1") (pin "AGND") (pinfunction "AGND_AGND") (pintype "bidirectional+no_connect"))
    )
    (net (code "87") (name "unconnected-(U23-Pad2)") (class "Default")
      (node (ref "U23") (pin "2") (pinfunction "2_2") (pintype "unspecified+no_connect"))
    )
  )
)
